# bbr18_wheel_motor_connector_board.net
KiCad netlist of a schematic drawn in Altium Designer
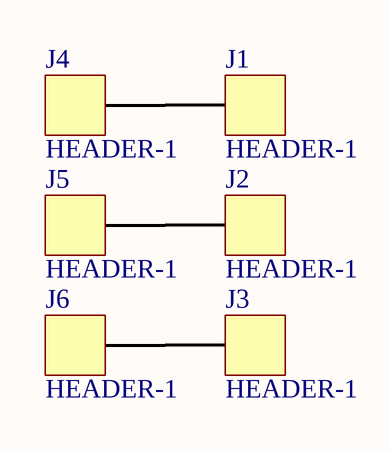
[diagram p0: bbr18_wheel_motor_connector_board.SchDoc]

(export (version "E")
  (design (tool "Eeschema 10.0.6"))
  (components
    (comp (ref "J1")
      (value "HEADER-1")
      (footprint "2MM-BULLET-PLUG-VIA")
      (libsource (lib "") (part "HEADER-1_1"))
    )
    (comp (ref "J2")
      (value "HEADER-1")
      (footprint "2MM-BULLET-PLUG-VIA")
      (libsource (lib "") (part "HEADER-1_1"))
    )
    (comp (ref "J3")
      (value "HEADER-1")
      (footprint "2MM-BULLET-PLUG-VIA")
      (libsource (lib "") (part "HEADER-1_1"))
    )
    (comp (ref "J4")
      (value "HEADER-1")
      (footprint "POWER-PAD-4x3")
      (libsource (lib "connectors") (part "HEADER-1"))
    )
    (comp (ref "J5")
      (value "HEADER-1")
      (footprint "POWER-PAD-4x3")
      (libsource (lib "connectors") (part "HEADER-1"))
    )
    (comp (ref "J6")
      (value "HEADER-1")
      (footprint "POWER-PAD-4x3")
      (libsource (lib "connectors") (part "HEADER-1"))
    )
  )
  (nets
    (net (code "1") (name "Net-(J1-Pad1)") (class "Default")
      (node (ref "J1") (pin "1") (pinfunction "1_1") (pintype "passive"))
      (node (ref "J4") (pin "1") (pinfunction "1_1") (pintype "passive"))
    )
    (net (code "2") (name "Net-(J2-Pad1)") (class "Default")
      (node (ref "J2") (pin "1") (pinfunction "1_1") (pintype "passive"))
      (node (ref "J5") (pin "1") (pinfunction "1_1") (pintype "passive"))
    )
    (net (code "3") (name "Net-(J3-Pad1)") (class "Default")
      (node (ref "J3") (pin "1") (pinfunction "1_1") (pintype "passive"))
      (node (ref "J6") (pin "1") (pinfunction "1_1") (pintype "passive"))
    )
  )
)
